# Estrella_Neopixel_PCBA.net
KiCad netlist of a schematic drawn in EAGLE
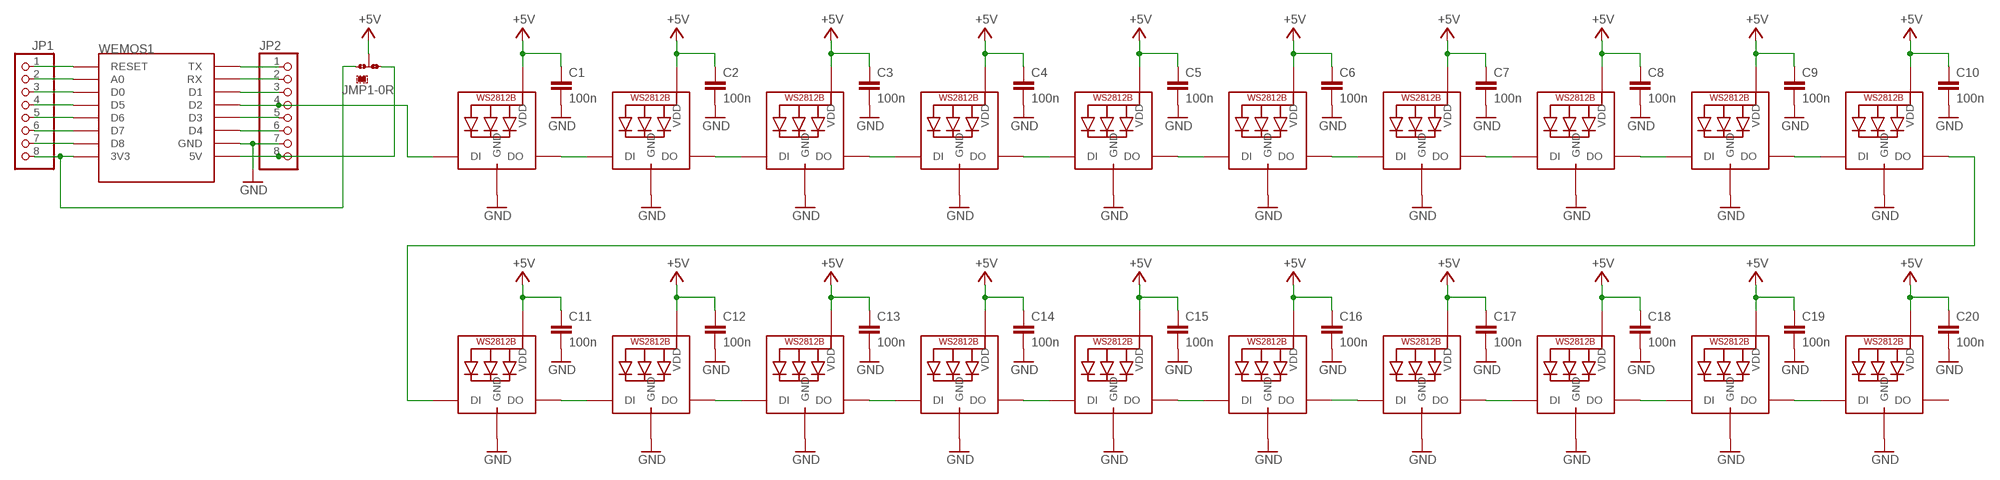
[diagram p0: schematic, sheet 1]

(export (version "E")
  (design (tool "Eeschema 10.0.6"))
  (components
    (comp (ref "C1")
      (value "100n")
      (footprint "eagle-import:C0805K")
      (libsource (lib "eagle-import") (part "C-EUC0805K"))
    )
    (comp (ref "C2")
      (value "100n")
      (footprint "eagle-import:C0805K")
      (libsource (lib "eagle-import") (part "C-EUC0805K"))
    )
    (comp (ref "C3")
      (value "100n")
      (footprint "eagle-import:C0805K")
      (libsource (lib "eagle-import") (part "C-EUC0805K"))
    )
    (comp (ref "C4")
      (value "100n")
      (footprint "eagle-import:C0805K")
      (libsource (lib "eagle-import") (part "C-EUC0805K"))
    )
    (comp (ref "C5")
      (value "100n")
      (footprint "eagle-import:C0805K")
      (libsource (lib "eagle-import") (part "C-EUC0805K"))
    )
    (comp (ref "C6")
      (value "100n")
      (footprint "eagle-import:C0805K")
      (libsource (lib "eagle-import") (part "C-EUC0805K"))
    )
    (comp (ref "C7")
      (value "100n")
      (footprint "eagle-import:C0805K")
      (libsource (lib "eagle-import") (part "C-EUC0805K"))
    )
    (comp (ref "C8")
      (value "100n")
      (footprint "eagle-import:C0805K")
      (libsource (lib "eagle-import") (part "C-EUC0805K"))
    )
    (comp (ref "C9")
      (value "100n")
      (footprint "eagle-import:C0805K")
      (libsource (lib "eagle-import") (part "C-EUC0805K"))
    )
    (comp (ref "C10")
      (value "100n")
      (footprint "eagle-import:C0805K")
      (libsource (lib "eagle-import") (part "C-EUC0805K"))
    )
    (comp (ref "C11")
      (value "100n")
      (footprint "eagle-import:C0805K")
      (libsource (lib "eagle-import") (part "C-EUC0805K"))
    )
    (comp (ref "C12")
      (value "100n")
      (footprint "eagle-import:C0805K")
      (libsource (lib "eagle-import") (part "C-EUC0805K"))
    )
    (comp (ref "C13")
      (value "100n")
      (footprint "eagle-import:C0805K")
      (libsource (lib "eagle-import") (part "C-EUC0805K"))
    )
    (comp (ref "C14")
      (value "100n")
      (footprint "eagle-import:C0805K")
      (libsource (lib "eagle-import") (part "C-EUC0805K"))
    )
    (comp (ref "C15")
      (value "100n")
      (footprint "eagle-import:C0805K")
      (libsource (lib "eagle-import") (part "C-EUC0805K"))
    )
    (comp (ref "C16")
      (value "100n")
      (footprint "eagle-import:C0805K")
      (libsource (lib "eagle-import") (part "C-EUC0805K"))
    )
    (comp (ref "C17")
      (value "100n")
      (footprint "eagle-import:C0805K")
      (libsource (lib "eagle-import") (part "C-EUC0805K"))
    )
    (comp (ref "C18")
      (value "100n")
      (footprint "eagle-import:C0805K")
      (libsource (lib "eagle-import") (part "C-EUC0805K"))
    )
    (comp (ref "C19")
      (value "100n")
      (footprint "eagle-import:C0805K")
      (libsource (lib "eagle-import") (part "C-EUC0805K"))
    )
    (comp (ref "C20")
      (value "100n")
      (footprint "eagle-import:C0805K")
      (libsource (lib "eagle-import") (part "C-EUC0805K"))
    )
    (comp (ref "JMP1")
      (value "0R-JUMPA")
      (footprint "eagle-import:A0R-JMP")
      (libsource (lib "eagle-import") (part "0R-JUMPA"))
    )
    (comp (ref "JP1")
      (value "PINHD-1X8")
      (footprint "eagle-import:1X08")
      (libsource (lib "eagle-import") (part "PINHD-1X8"))
    )
    (comp (ref "JP2")
      (value "PINHD-1X8")
      (footprint "eagle-import:1X08")
      (libsource (lib "eagle-import") (part "PINHD-1X8"))
    )
    (comp (ref "LED1")
      (value "WS2812B_5050N")
      (footprint "eagle-import:WS2812B-NARROW")
      (libsource (lib "eagle-import") (part "WS2812B_5050N"))
    )
    (comp (ref "LED2")
      (value "WS2812B_5050N")
      (footprint "eagle-import:WS2812B-NARROW")
      (libsource (lib "eagle-import") (part "WS2812B_5050N"))
    )
    (comp (ref "LED3")
      (value "WS2812B_5050N")
      (footprint "eagle-import:WS2812B-NARROW")
      (libsource (lib "eagle-import") (part "WS2812B_5050N"))
    )
    (comp (ref "LED4")
      (value "WS2812B_5050N")
      (footprint "eagle-import:WS2812B-NARROW")
      (libsource (lib "eagle-import") (part "WS2812B_5050N"))
    )
    (comp (ref "LED5")
      (value "WS2812B_5050N")
      (footprint "eagle-import:WS2812B-NARROW")
      (libsource (lib "eagle-import") (part "WS2812B_5050N"))
    )
    (comp (ref "LED6")
      (value "WS2812B_5050N")
      (footprint "eagle-import:WS2812B-NARROW")
      (libsource (lib "eagle-import") (part "WS2812B_5050N"))
    )
    (comp (ref "LED7")
      (value "WS2812B_5050N")
      (footprint "eagle-import:WS2812B-NARROW")
      (libsource (lib "eagle-import") (part "WS2812B_5050N"))
    )
    (comp (ref "LED8")
      (value "WS2812B_5050N")
      (footprint "eagle-import:WS2812B-NARROW")
      (libsource (lib "eagle-import") (part "WS2812B_5050N"))
    )
    (comp (ref "LED9")
      (value "WS2812B_5050N")
      (footprint "eagle-import:WS2812B-NARROW")
      (libsource (lib "eagle-import") (part "WS2812B_5050N"))
    )
    (comp (ref "LED10")
      (value "WS2812B_5050N")
      (footprint "eagle-import:WS2812B-NARROW")
      (libsource (lib "eagle-import") (part "WS2812B_5050N"))
    )
    (comp (ref "LED11")
      (value "WS2812B_5050N")
      (footprint "eagle-import:WS2812B-NARROW")
      (libsource (lib "eagle-import") (part "WS2812B_5050N"))
    )
    (comp (ref "LED12")
      (value "WS2812B_5050N")
      (footprint "eagle-import:WS2812B-NARROW")
      (libsource (lib "eagle-import") (part "WS2812B_5050N"))
    )
    (comp (ref "LED13")
      (value "WS2812B_5050N")
      (footprint "eagle-import:WS2812B-NARROW")
      (libsource (lib "eagle-import") (part "WS2812B_5050N"))
    )
    (comp (ref "LED14")
      (value "WS2812B_5050N")
      (footprint "eagle-import:WS2812B-NARROW")
      (libsource (lib "eagle-import") (part "WS2812B_5050N"))
    )
    (comp (ref "LED15")
      (value "WS2812B_5050N")
      (footprint "eagle-import:WS2812B-NARROW")
      (libsource (lib "eagle-import") (part "WS2812B_5050N"))
    )
    (comp (ref "LED16")
      (value "WS2812B_5050N")
      (footprint "eagle-import:WS2812B-NARROW")
      (libsource (lib "eagle-import") (part "WS2812B_5050N"))
    )
    (comp (ref "LED17")
      (value "WS2812B_5050N")
      (footprint "eagle-import:WS2812B-NARROW")
      (libsource (lib "eagle-import") (part "WS2812B_5050N"))
    )
    (comp (ref "LED18")
      (value "WS2812B_5050N")
      (footprint "eagle-import:WS2812B-NARROW")
      (libsource (lib "eagle-import") (part "WS2812B_5050N"))
    )
    (comp (ref "LED19")
      (value "WS2812B_5050N")
      (footprint "eagle-import:WS2812B-NARROW")
      (libsource (lib "eagle-import") (part "WS2812B_5050N"))
    )
    (comp (ref "LED20")
      (value "WS2812B_5050N")
      (footprint "eagle-import:WS2812B-NARROW")
      (libsource (lib "eagle-import") (part "WS2812B_5050N"))
    )
    (comp (ref "WEMOS1")
      (value "WEMOS-D1-MINI")
      (footprint "eagle-import:WEMOS-D1-MINI")
      (libsource (lib "eagle-import") (part "WEMOS-D1-MINI"))
    )
  )
  (nets
    (net (code "1") (name "+5V") (class "Default")
      (node (ref "C1") (pin "1") (pinfunction "1_1") (pintype "passive"))
      (node (ref "C10") (pin "1") (pinfunction "1_1") (pintype "passive"))
      (node (ref "C11") (pin "1") (pinfunction "1_1") (pintype "passive"))
      (node (ref "C12") (pin "1") (pinfunction "1_1") (pintype "passive"))
      (node (ref "C13") (pin "1") (pinfunction "1_1") (pintype "passive"))
      (node (ref "C14") (pin "1") (pinfunction "1_1") (pintype "passive"))
      (node (ref "C15") (pin "1") (pinfunction "1_1") (pintype "passive"))
      (node (ref "C16") (pin "1") (pinfunction "1_1") (pintype "passive"))
      (node (ref "C17") (pin "1") (pinfunction "1_1") (pintype "passive"))
      (node (ref "C18") (pin "1") (pinfunction "1_1") (pintype "passive"))
      (node (ref "C19") (pin "1") (pinfunction "1_1") (pintype "passive"))
      (node (ref "C2") (pin "1") (pinfunction "1_1") (pintype "passive"))
      (node (ref "C20") (pin "1") (pinfunction "1_1") (pintype "passive"))
      (node (ref "C3") (pin "1") (pinfunction "1_1") (pintype "passive"))
      (node (ref "C4") (pin "1") (pinfunction "1_1") (pintype "passive"))
      (node (ref "C5") (pin "1") (pinfunction "1_1") (pintype "passive"))
      (node (ref "C6") (pin "1") (pinfunction "1_1") (pintype "passive"))
      (node (ref "C7") (pin "1") (pinfunction "1_1") (pintype "passive"))
      (node (ref "C8") (pin "1") (pinfunction "1_1") (pintype "passive"))
      (node (ref "C9") (pin "1") (pinfunction "1_1") (pintype "passive"))
      (node (ref "JMP1") (pin "2") (pinfunction "2_2") (pintype "passive"))
      (node (ref "LED1") (pin "1-VDD") (pinfunction "VDD_1-VDD") (pintype "power_in"))
      (node (ref "LED10") (pin "1-VDD") (pinfunction "VDD_1-VDD") (pintype "power_in"))
      (node (ref "LED11") (pin "1-VDD") (pinfunction "VDD_1-VDD") (pintype "power_in"))
      (node (ref "LED12") (pin "1-VDD") (pinfunction "VDD_1-VDD") (pintype "power_in"))
      (node (ref "LED13") (pin "1-VDD") (pinfunction "VDD_1-VDD") (pintype "power_in"))
      (node (ref "LED14") (pin "1-VDD") (pinfunction "VDD_1-VDD") (pintype "power_in"))
      (node (ref "LED15") (pin "1-VDD") (pinfunction "VDD_1-VDD") (pintype "power_in"))
      (node (ref "LED16") (pin "1-VDD") (pinfunction "VDD_1-VDD") (pintype "power_in"))
      (node (ref "LED17") (pin "1-VDD") (pinfunction "VDD_1-VDD") (pintype "power_in"))
      (node (ref "LED18") (pin "1-VDD") (pinfunction "VDD_1-VDD") (pintype "power_in"))
      (node (ref "LED19") (pin "1-VDD") (pinfunction "VDD_1-VDD") (pintype "power_in"))
      (node (ref "LED2") (pin "1-VDD") (pinfunction "VDD_1-VDD") (pintype "power_in"))
      (node (ref "LED20") (pin "1-VDD") (pinfunction "VDD_1-VDD") (pintype "power_in"))
      (node (ref "LED3") (pin "1-VDD") (pinfunction "VDD_1-VDD") (pintype "power_in"))
      (node (ref "LED4") (pin "1-VDD") (pinfunction "VDD_1-VDD") (pintype "power_in"))
      (node (ref "LED5") (pin "1-VDD") (pinfunction "VDD_1-VDD") (pintype "power_in"))
      (node (ref "LED6") (pin "1-VDD") (pinfunction "VDD_1-VDD") (pintype "power_in"))
      (node (ref "LED7") (pin "1-VDD") (pinfunction "VDD_1-VDD") (pintype "power_in"))
      (node (ref "LED8") (pin "1-VDD") (pinfunction "VDD_1-VDD") (pintype "power_in"))
      (node (ref "LED9") (pin "1-VDD") (pinfunction "VDD_1-VDD") (pintype "power_in"))
    )
    (net (code "2") (name "GND") (class "Default")
      (node (ref "C1") (pin "2") (pinfunction "2_2") (pintype "passive"))
      (node (ref "C10") (pin "2") (pinfunction "2_2") (pintype "passive"))
      (node (ref "C11") (pin "2") (pinfunction "2_2") (pintype "passive"))
      (node (ref "C12") (pin "2") (pinfunction "2_2") (pintype "passive"))
      (node (ref "C13") (pin "2") (pinfunction "2_2") (pintype "passive"))
      (node (ref "C14") (pin "2") (pinfunction "2_2") (pintype "passive"))
      (node (ref "C15") (pin "2") (pinfunction "2_2") (pintype "passive"))
      (node (ref "C16") (pin "2") (pinfunction "2_2") (pintype "passive"))
      (node (ref "C17") (pin "2") (pinfunction "2_2") (pintype "passive"))
      (node (ref "C18") (pin "2") (pinfunction "2_2") (pintype "passive"))
      (node (ref "C19") (pin "2") (pinfunction "2_2") (pintype "passive"))
      (node (ref "C2") (pin "2") (pinfunction "2_2") (pintype "passive"))
      (node (ref "C20") (pin "2") (pinfunction "2_2") (pintype "passive"))
      (node (ref "C3") (pin "2") (pinfunction "2_2") (pintype "passive"))
      (node (ref "C4") (pin "2") (pinfunction "2_2") (pintype "passive"))
      (node (ref "C5") (pin "2") (pinfunction "2_2") (pintype "passive"))
      (node (ref "C6") (pin "2") (pinfunction "2_2") (pintype "passive"))
      (node (ref "C7") (pin "2") (pinfunction "2_2") (pintype "passive"))
      (node (ref "C8") (pin "2") (pinfunction "2_2") (pintype "passive"))
      (node (ref "C9") (pin "2") (pinfunction "2_2") (pintype "passive"))
      (node (ref "JP2") (pin "7") (pinfunction "7_7") (pintype "passive"))
      (node (ref "LED1") (pin "3-GND") (pinfunction "GND_3-GND") (pintype "power_in"))
      (node (ref "LED10") (pin "3-GND") (pinfunction "GND_3-GND") (pintype "power_in"))
      (node (ref "LED11") (pin "3-GND") (pinfunction "GND_3-GND") (pintype "power_in"))
      (node (ref "LED12") (pin "3-GND") (pinfunction "GND_3-GND") (pintype "power_in"))
      (node (ref "LED13") (pin "3-GND") (pinfunction "GND_3-GND") (pintype "power_in"))
      (node (ref "LED14") (pin "3-GND") (pinfunction "GND_3-GND") (pintype "power_in"))
      (node (ref "LED15") (pin "3-GND") (pinfunction "GND_3-GND") (pintype "power_in"))
      (node (ref "LED16") (pin "3-GND") (pinfunction "GND_3-GND") (pintype "power_in"))
      (node (ref "LED17") (pin "3-GND") (pinfunction "GND_3-GND") (pintype "power_in"))
      (node (ref "LED18") (pin "3-GND") (pinfunction "GND_3-GND") (pintype "power_in"))
      (node (ref "LED19") (pin "3-GND") (pinfunction "GND_3-GND") (pintype "power_in"))
      (node (ref "LED2") (pin "3-GND") (pinfunction "GND_3-GND") (pintype "power_in"))
      (node (ref "LED20") (pin "3-GND") (pinfunction "GND_3-GND") (pintype "power_in"))
      (node (ref "LED3") (pin "3-GND") (pinfunction "GND_3-GND") (pintype "power_in"))
      (node (ref "LED4") (pin "3-GND") (pinfunction "GND_3-GND") (pintype "power_in"))
      (node (ref "LED5") (pin "3-GND") (pinfunction "GND_3-GND") (pintype "power_in"))
      (node (ref "LED6") (pin "3-GND") (pinfunction "GND_3-GND") (pintype "power_in"))
      (node (ref "LED7") (pin "3-GND") (pinfunction "GND_3-GND") (pintype "power_in"))
      (node (ref "LED8") (pin "3-GND") (pinfunction "GND_3-GND") (pintype "power_in"))
      (node (ref "LED9") (pin "3-GND") (pinfunction "GND_3-GND") (pintype "power_in"))
      (node (ref "WEMOS1") (pin "GND") (pinfunction "GND_GND") (pintype "bidirectional"))
    )
    (net (code "3") (name "Net-(JMP1-Pad1)") (class "Default")
      (node (ref "JMP1") (pin "1") (pinfunction "1_1") (pintype "passive"))
      (node (ref "JP1") (pin "8") (pinfunction "8_8") (pintype "passive"))
      (node (ref "WEMOS1") (pin "3V3") (pinfunction "3V3_3V3") (pintype "bidirectional"))
    )
    (net (code "4") (name "Net-(JMP1-Pad3)") (class "Default")
      (node (ref "JMP1") (pin "3") (pinfunction "3_3") (pintype "passive"))
      (node (ref "JP2") (pin "8") (pinfunction "8_8") (pintype "passive"))
      (node (ref "WEMOS1") (pin "5V") (pinfunction "5V_5V") (pintype "bidirectional"))
    )
    (net (code "5") (name "Net-(JP1-Pad1)") (class "Default")
      (node (ref "JP1") (pin "1") (pinfunction "1_1") (pintype "passive"))
      (node (ref "WEMOS1") (pin "RESET") (pinfunction "RESET_RESET") (pintype "bidirectional"))
    )
    (net (code "6") (name "Net-(JP1-Pad2)") (class "Default")
      (node (ref "JP1") (pin "2") (pinfunction "2_2") (pintype "passive"))
      (node (ref "WEMOS1") (pin "A0") (pinfunction "A0_A0") (pintype "bidirectional"))
    )
    (net (code "7") (name "Net-(JP1-Pad3)") (class "Default")
      (node (ref "JP1") (pin "3") (pinfunction "3_3") (pintype "passive"))
      (node (ref "WEMOS1") (pin "D0") (pinfunction "D0_D0") (pintype "bidirectional"))
    )
    (net (code "8") (name "Net-(JP1-Pad4)") (class "Default")
      (node (ref "JP1") (pin "4") (pinfunction "4_4") (pintype "passive"))
      (node (ref "WEMOS1") (pin "D5") (pinfunction "D5_D5") (pintype "bidirectional"))
    )
    (net (code "9") (name "Net-(JP1-Pad5)") (class "Default")
      (node (ref "JP1") (pin "5") (pinfunction "5_5") (pintype "passive"))
      (node (ref "WEMOS1") (pin "D6") (pinfunction "D6_D6") (pintype "bidirectional"))
    )
    (net (code "10") (name "Net-(JP1-Pad6)") (class "Default")
      (node (ref "JP1") (pin "6") (pinfunction "6_6") (pintype "passive"))
      (node (ref "WEMOS1") (pin "D7") (pinfunction "D7_D7") (pintype "bidirectional"))
    )
    (net (code "11") (name "Net-(JP1-Pad7)") (class "Default")
      (node (ref "JP1") (pin "7") (pinfunction "7_7") (pintype "passive"))
      (node (ref "WEMOS1") (pin "D8") (pinfunction "D8_D8") (pintype "bidirectional"))
    )
    (net (code "12") (name "Net-(JP2-Pad1)") (class "Default")
      (node (ref "JP2") (pin "1") (pinfunction "1_1") (pintype "passive"))
      (node (ref "WEMOS1") (pin "TX") (pinfunction "TX_TX") (pintype "bidirectional"))
    )
    (net (code "13") (name "Net-(JP2-Pad2)") (class "Default")
      (node (ref "JP2") (pin "2") (pinfunction "2_2") (pintype "passive"))
      (node (ref "WEMOS1") (pin "RX") (pinfunction "RX_RX") (pintype "bidirectional"))
    )
    (net (code "14") (name "Net-(JP2-Pad3)") (class "Default")
      (node (ref "JP2") (pin "3") (pinfunction "3_3") (pintype "passive"))
      (node (ref "WEMOS1") (pin "D1") (pinfunction "D1_D1") (pintype "bidirectional"))
    )
    (net (code "15") (name "Net-(JP2-Pad5)") (class "Default")
      (node (ref "JP2") (pin "5") (pinfunction "5_5") (pintype "passive"))
      (node (ref "WEMOS1") (pin "D3") (pinfunction "D3_D3") (pintype "bidirectional"))
    )
    (net (code "16") (name "Net-(JP2-Pad6)") (class "Default")
      (node (ref "JP2") (pin "6") (pinfunction "6_6") (pintype "passive"))
      (node (ref "WEMOS1") (pin "D4") (pinfunction "D4_D4") (pintype "bidirectional"))
    )
    (net (code "17") (name "Net-(LED1-DI)") (class "Default")
      (node (ref "JP2") (pin "4") (pinfunction "4_4") (pintype "passive"))
      (node (ref "LED1") (pin "4-DIN") (pinfunction "DI_4-DIN") (pintype "input"))
      (node (ref "WEMOS1") (pin "D2") (pinfunction "D2_D2") (pintype "bidirectional"))
    )
    (net (code "18") (name "Net-(LED1-DO)") (class "Default")
      (node (ref "LED1") (pin "2-DOUT") (pinfunction "DO_2-DOUT") (pintype "output"))
      (node (ref "LED2") (pin "4-DIN") (pinfunction "DI_4-DIN") (pintype "input"))
    )
    (net (code "19") (name "Net-(LED2-DO)") (class "Default")
      (node (ref "LED2") (pin "2-DOUT") (pinfunction "DO_2-DOUT") (pintype "output"))
      (node (ref "LED3") (pin "4-DIN") (pinfunction "DI_4-DIN") (pintype "input"))
    )
    (net (code "20") (name "Net-(LED3-DO)") (class "Default")
      (node (ref "LED3") (pin "2-DOUT") (pinfunction "DO_2-DOUT") (pintype "output"))
      (node (ref "LED4") (pin "4-DIN") (pinfunction "DI_4-DIN") (pintype "input"))
    )
    (net (code "21") (name "Net-(LED4-DO)") (class "Default")
      (node (ref "LED4") (pin "2-DOUT") (pinfunction "DO_2-DOUT") (pintype "output"))
      (node (ref "LED5") (pin "4-DIN") (pinfunction "DI_4-DIN") (pintype "input"))
    )
    (net (code "22") (name "Net-(LED5-DO)") (class "Default")
      (node (ref "LED5") (pin "2-DOUT") (pinfunction "DO_2-DOUT") (pintype "output"))
      (node (ref "LED6") (pin "4-DIN") (pinfunction "DI_4-DIN") (pintype "input"))
    )
    (net (code "23") (name "Net-(LED6-DO)") (class "Default")
      (node (ref "LED6") (pin "2-DOUT") (pinfunction "DO_2-DOUT") (pintype "output"))
      (node (ref "LED7") (pin "4-DIN") (pinfunction "DI_4-DIN") (pintype "input"))
    )
    (net (code "24") (name "Net-(LED7-DO)") (class "Default")
      (node (ref "LED7") (pin "2-DOUT") (pinfunction "DO_2-DOUT") (pintype "output"))
      (node (ref "LED8") (pin "4-DIN") (pinfunction "DI_4-DIN") (pintype "input"))
    )
    (net (code "25") (name "Net-(LED8-DO)") (class "Default")
      (node (ref "LED8") (pin "2-DOUT") (pinfunction "DO_2-DOUT") (pintype "output"))
      (node (ref "LED9") (pin "4-DIN") (pinfunction "DI_4-DIN") (pintype "input"))
    )
    (net (code "26") (name "Net-(LED10-DI)") (class "Default")
      (node (ref "LED10") (pin "4-DIN") (pinfunction "DI_4-DIN") (pintype "input"))
      (node (ref "LED9") (pin "2-DOUT") (pinfunction "DO_2-DOUT") (pintype "output"))
    )
    (net (code "27") (name "Net-(LED10-DO)") (class "Default")
      (node (ref "LED10") (pin "2-DOUT") (pinfunction "DO_2-DOUT") (pintype "output"))
      (node (ref "LED11") (pin "4-DIN") (pinfunction "DI_4-DIN") (pintype "input"))
    )
    (net (code "28") (name "Net-(LED11-DO)") (class "Default")
      (node (ref "LED11") (pin "2-DOUT") (pinfunction "DO_2-DOUT") (pintype "output"))
      (node (ref "LED12") (pin "4-DIN") (pinfunction "DI_4-DIN") (pintype "input"))
    )
    (net (code "29") (name "Net-(LED12-DO)") (class "Default")
      (node (ref "LED12") (pin "2-DOUT") (pinfunction "DO_2-DOUT") (pintype "output"))
      (node (ref "LED13") (pin "4-DIN") (pinfunction "DI_4-DIN") (pintype "input"))
    )
    (net (code "30") (name "Net-(LED13-DO)") (class "Default")
      (node (ref "LED13") (pin "2-DOUT") (pinfunction "DO_2-DOUT") (pintype "output"))
      (node (ref "LED14") (pin "4-DIN") (pinfunction "DI_4-DIN") (pintype "input"))
    )
    (net (code "31") (name "Net-(LED14-DO)") (class "Default")
      (node (ref "LED14") (pin "2-DOUT") (pinfunction "DO_2-DOUT") (pintype "output"))
      (node (ref "LED15") (pin "4-DIN") (pinfunction "DI_4-DIN") (pintype "input"))
    )
    (net (code "32") (name "Net-(LED15-DO)") (class "Default")
      (node (ref "LED15") (pin "2-DOUT") (pinfunction "DO_2-DOUT") (pintype "output"))
      (node (ref "LED16") (pin "4-DIN") (pinfunction "DI_4-DIN") (pintype "input"))
    )
    (net (code "33") (name "Net-(LED16-DO)") (class "Default")
      (node (ref "LED16") (pin "2-DOUT") (pinfunction "DO_2-DOUT") (pintype "output"))
      (node (ref "LED17") (pin "4-DIN") (pinfunction "DI_4-DIN") (pintype "input"))
    )
    (net (code "34") (name "Net-(LED17-DO)") (class "Default")
      (node (ref "LED17") (pin "2-DOUT") (pinfunction "DO_2-DOUT") (pintype "output"))
      (node (ref "LED18") (pin "4-DIN") (pinfunction "DI_4-DIN") (pintype "input"))
    )
    (net (code "35") (name "Net-(LED18-DO)") (class "Default")
      (node (ref "LED18") (pin "2-DOUT") (pinfunction "DO_2-DOUT") (pintype "output"))
      (node (ref "LED19") (pin "4-DIN") (pinfunction "DI_4-DIN") (pintype "input"))
    )
    (net (code "36") (name "Net-(LED19-DO)") (class "Default")
      (node (ref "LED19") (pin "2-DOUT") (pinfunction "DO_2-DOUT") (pintype "output"))
      (node (ref "LED20") (pin "4-DIN") (pinfunction "DI_4-DIN") (pintype "input"))
    )
    (net (code "37") (name "unconnected-(LED20-DO-Pad2-DOUT)") (class "Default")
      (node (ref "LED20") (pin "2-DOUT") (pinfunction "DO_2-DOUT") (pintype "output"))
    )
  )
)
